# brd-relays2.net
KiCad netlist of a schematic drawn in EAGLE
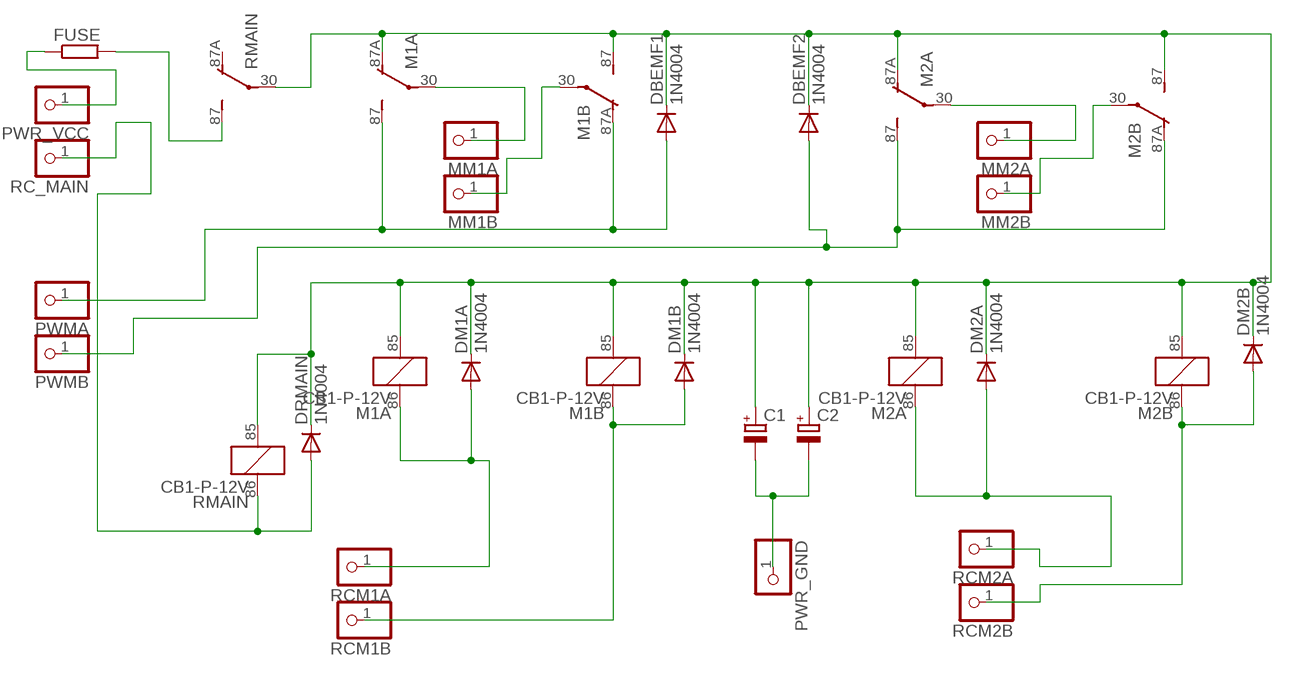
[diagram p0: schematic, sheet 1]

(export (version "E")
  (design (tool "Eeschema 10.0.6"))
  (components
    (comp (ref "C1")
      (value "CPOL-EUE5-13")
      (footprint "eagle-import:E5-13")
      (libsource (lib "eagle-import") (part "CPOL-EUE5-13"))
    )
    (comp (ref "C2")
      (value "CPOL-EUE5-13")
      (footprint "eagle-import:E5-13")
      (libsource (lib "eagle-import") (part "CPOL-EUE5-13"))
    )
    (comp (ref "DBEMF1")
      (value "1N4004")
      (footprint "eagle-import:DO41-10")
      (libsource (lib "eagle-import") (part "1N4004"))
    )
    (comp (ref "DBEMF2")
      (value "1N4004")
      (footprint "eagle-import:DO41-10")
      (libsource (lib "eagle-import") (part "1N4004"))
    )
    (comp (ref "DM1A")
      (value "1N4004")
      (footprint "eagle-import:DO41-10")
      (libsource (lib "eagle-import") (part "1N4004"))
    )
    (comp (ref "DM1B")
      (value "1N4004")
      (footprint "eagle-import:DO41-10")
      (libsource (lib "eagle-import") (part "1N4004"))
    )
    (comp (ref "DM2A")
      (value "1N4004")
      (footprint "eagle-import:DO41-10")
      (libsource (lib "eagle-import") (part "1N4004"))
    )
    (comp (ref "DM2B")
      (value "1N4004")
      (footprint "eagle-import:DO41-10")
      (libsource (lib "eagle-import") (part "1N4004"))
    )
    (comp (ref "DRMAIN")
      (value "1N4004")
      (footprint "eagle-import:DO41-10")
      (libsource (lib "eagle-import") (part "1N4004"))
    )
    (comp (ref "FUSE")
      (value "R-EU_0207/10")
      (footprint "eagle-import:FUSE_PACK1")
      (libsource (lib "eagle-import") (part "R-EU_0207/10"))
    )
    (comp (ref "M1A")
      (value "CB1-P-12V")
      (footprint "eagle-import:CB1")
      (fields (field (name "MF") "AROMAT/ MATSUSHITA"))
      (libsource (lib "eagle-import") (part "CB1-P-12V"))
    )
    (comp (ref "M1B")
      (value "CB1-P-12V")
      (footprint "eagle-import:CB1")
      (fields (field (name "MF") "AROMAT/ MATSUSHITA"))
      (libsource (lib "eagle-import") (part "CB1-P-12V"))
    )
    (comp (ref "M2A")
      (value "CB1-P-12V")
      (footprint "eagle-import:CB1")
      (fields (field (name "MF") "AROMAT/ MATSUSHITA"))
      (libsource (lib "eagle-import") (part "CB1-P-12V"))
    )
    (comp (ref "M2B")
      (value "CB1-P-12V")
      (footprint "eagle-import:CB1")
      (fields (field (name "MF") "AROMAT/ MATSUSHITA"))
      (libsource (lib "eagle-import") (part "CB1-P-12V"))
    )
    (comp (ref "MM1A")
      (value "PINHD-1X1")
      (footprint "eagle-import:1X01")
      (libsource (lib "eagle-import") (part "PINHD-1X1"))
    )
    (comp (ref "MM1B")
      (value "PINHD-1X1")
      (footprint "eagle-import:1X01")
      (libsource (lib "eagle-import") (part "PINHD-1X1"))
    )
    (comp (ref "MM2A")
      (value "PINHD-1X1")
      (footprint "eagle-import:1X01")
      (libsource (lib "eagle-import") (part "PINHD-1X1"))
    )
    (comp (ref "MM2B")
      (value "PINHD-1X1")
      (footprint "eagle-import:1X01")
      (libsource (lib "eagle-import") (part "PINHD-1X1"))
    )
    (comp (ref "PWMA")
      (value "PINHD-1X1")
      (footprint "eagle-import:1X01")
      (libsource (lib "eagle-import") (part "PINHD-1X1"))
    )
    (comp (ref "PWMB")
      (value "PINHD-1X1")
      (footprint "eagle-import:1X01")
      (libsource (lib "eagle-import") (part "PINHD-1X1"))
    )
    (comp (ref "PWR_GND")
      (value "PINHD-1X1")
      (footprint "eagle-import:1X01")
      (libsource (lib "eagle-import") (part "PINHD-1X1"))
    )
    (comp (ref "PWR_VCC")
      (value "PINHD-1X1")
      (footprint "eagle-import:1X01")
      (libsource (lib "eagle-import") (part "PINHD-1X1"))
    )
    (comp (ref "RCM1A")
      (value "PINHD-1X1")
      (footprint "eagle-import:1X01")
      (libsource (lib "eagle-import") (part "PINHD-1X1"))
    )
    (comp (ref "RCM1B")
      (value "PINHD-1X1")
      (footprint "eagle-import:1X01")
      (libsource (lib "eagle-import") (part "PINHD-1X1"))
    )
    (comp (ref "RCM2A")
      (value "PINHD-1X1")
      (footprint "eagle-import:1X01")
      (libsource (lib "eagle-import") (part "PINHD-1X1"))
    )
    (comp (ref "RCM2B")
      (value "PINHD-1X1")
      (footprint "eagle-import:1X01")
      (libsource (lib "eagle-import") (part "PINHD-1X1"))
    )
    (comp (ref "RC_MAIN")
      (value "PINHD-1X1")
      (footprint "eagle-import:1X01")
      (libsource (lib "eagle-import") (part "PINHD-1X1"))
    )
    (comp (ref "RMAIN")
      (value "CB1-P-12V")
      (footprint "eagle-import:CB1")
      (fields (field (name "MF") "AROMAT/ MATSUSHITA"))
      (libsource (lib "eagle-import") (part "CB1-P-12V"))
    )
  )
  (nets
    (net (code "1") (name "Net-(C1-Pad-)") (class "Default")
      (node (ref "C1") (pin "-") (pinfunction "-_-") (pintype "passive"))
      (node (ref "C2") (pin "-") (pinfunction "-_-") (pintype "passive"))
      (node (ref "PWR_GND") (pin "1") (pinfunction "1_1") (pintype "passive"))
    )
    (net (code "2") (name "Net-(FUSE-Pad1)") (class "Default")
      (node (ref "FUSE") (pin "1") (pinfunction "1_1") (pintype "passive"))
      (node (ref "PWR_VCC") (pin "1") (pinfunction "1_1") (pintype "passive"))
    )
    (net (code "3") (name "Net-(M1AA-1)") (class "Default")
      (node (ref "DM1A") (pin "A") (pinfunction "A_A") (pintype "passive"))
      (node (ref "M1A") (pin "86") (pinfunction "1_86") (pintype "passive"))
      (node (ref "RCM1A") (pin "1") (pinfunction "1_1") (pintype "passive"))
    )
    (net (code "4") (name "Net-(M1AA-2)") (class "Default")
      (node (ref "C1") (pin "+") (pinfunction "+_+") (pintype "passive"))
      (node (ref "C2") (pin "+") (pinfunction "+_+") (pintype "passive"))
      (node (ref "DBEMF1") (pin "C") (pinfunction "C_C") (pintype "passive"))
      (node (ref "DBEMF2") (pin "C") (pinfunction "C_C") (pintype "passive"))
      (node (ref "DM1A") (pin "C") (pinfunction "C_C") (pintype "passive"))
      (node (ref "DM1B") (pin "C") (pinfunction "C_C") (pintype "passive"))
      (node (ref "DM2A") (pin "C") (pinfunction "C_C") (pintype "passive"))
      (node (ref "DM2B") (pin "C") (pinfunction "C_C") (pintype "passive"))
      (node (ref "DRMAIN") (pin "C") (pinfunction "C_C") (pintype "passive"))
      (node (ref "M1A") (pin "85") (pinfunction "2_85") (pintype "passive"))
      (node (ref "M1A") (pin "87A") (pinfunction "O_87A") (pintype "passive"))
      (node (ref "M1B") (pin "85") (pinfunction "2_85") (pintype "passive"))
      (node (ref "M1B") (pin "87") (pinfunction "S_87") (pintype "passive"))
      (node (ref "M2A") (pin "85") (pinfunction "2_85") (pintype "passive"))
      (node (ref "M2A") (pin "87A") (pinfunction "O_87A") (pintype "passive"))
      (node (ref "M2B") (pin "85") (pinfunction "2_85") (pintype "passive"))
      (node (ref "M2B") (pin "87") (pinfunction "S_87") (pintype "passive"))
      (node (ref "RMAIN") (pin "30") (pinfunction "P_30") (pintype "passive"))
      (node (ref "RMAIN") (pin "85") (pinfunction "2_85") (pintype "passive"))
    )
    (net (code "5") (name "Net-(M1AB-P)") (class "Default")
      (node (ref "M1A") (pin "30") (pinfunction "P_30") (pintype "passive"))
      (node (ref "MM1A") (pin "1") (pinfunction "1_1") (pintype "passive"))
    )
    (net (code "6") (name "Net-(M1AB-S)") (class "Default")
      (node (ref "DBEMF1") (pin "A") (pinfunction "A_A") (pintype "passive"))
      (node (ref "M1A") (pin "87") (pinfunction "S_87") (pintype "passive"))
      (node (ref "M1B") (pin "87A") (pinfunction "O_87A") (pintype "passive"))
      (node (ref "PWMA") (pin "1") (pinfunction "1_1") (pintype "passive"))
    )
    (net (code "7") (name "Net-(M1BA-1)") (class "Default")
      (node (ref "DM1B") (pin "A") (pinfunction "A_A") (pintype "passive"))
      (node (ref "M1B") (pin "86") (pinfunction "1_86") (pintype "passive"))
      (node (ref "RCM1B") (pin "1") (pinfunction "1_1") (pintype "passive"))
    )
    (net (code "8") (name "Net-(M1BB-P)") (class "Default")
      (node (ref "M1B") (pin "30") (pinfunction "P_30") (pintype "passive"))
      (node (ref "MM1B") (pin "1") (pinfunction "1_1") (pintype "passive"))
    )
    (net (code "9") (name "Net-(M2AA-1)") (class "Default")
      (node (ref "DM2A") (pin "A") (pinfunction "A_A") (pintype "passive"))
      (node (ref "M2A") (pin "86") (pinfunction "1_86") (pintype "passive"))
      (node (ref "RCM2A") (pin "1") (pinfunction "1_1") (pintype "passive"))
    )
    (net (code "10") (name "Net-(M2AB-P)") (class "Default")
      (node (ref "M2A") (pin "30") (pinfunction "P_30") (pintype "passive"))
      (node (ref "MM2A") (pin "1") (pinfunction "1_1") (pintype "passive"))
    )
    (net (code "11") (name "Net-(M2AB-S)") (class "Default")
      (node (ref "DBEMF2") (pin "A") (pinfunction "A_A") (pintype "passive"))
      (node (ref "M2A") (pin "87") (pinfunction "S_87") (pintype "passive"))
      (node (ref "M2B") (pin "87A") (pinfunction "O_87A") (pintype "passive"))
      (node (ref "PWMB") (pin "1") (pinfunction "1_1") (pintype "passive"))
    )
    (net (code "12") (name "Net-(M2BA-1)") (class "Default")
      (node (ref "DM2B") (pin "A") (pinfunction "A_A") (pintype "passive"))
      (node (ref "M2B") (pin "86") (pinfunction "1_86") (pintype "passive"))
      (node (ref "RCM2B") (pin "1") (pinfunction "1_1") (pintype "passive"))
    )
    (net (code "13") (name "Net-(M2BB-P)") (class "Default")
      (node (ref "M2B") (pin "30") (pinfunction "P_30") (pintype "passive"))
      (node (ref "MM2B") (pin "1") (pinfunction "1_1") (pintype "passive"))
    )
    (net (code "14") (name "Net-(RMAINA-1)") (class "Default")
      (node (ref "DRMAIN") (pin "A") (pinfunction "A_A") (pintype "passive"))
      (node (ref "RC_MAIN") (pin "1") (pinfunction "1_1") (pintype "passive"))
      (node (ref "RMAIN") (pin "86") (pinfunction "1_86") (pintype "passive"))
    )
    (net (code "15") (name "Net-(RMAINB-S)") (class "Default")
      (node (ref "FUSE") (pin "2") (pinfunction "2_2") (pintype "passive"))
      (node (ref "RMAIN") (pin "87") (pinfunction "S_87") (pintype "passive"))
    )
    (net (code "16") (name "unconnected-(RMAINB-O-Pad87A)") (class "Default")
      (node (ref "RMAIN") (pin "87A") (pinfunction "O_87A") (pintype "passive"))
    )
  )
)
